# headers.net
KiCad netlist of a schematic drawn in Altium Designer
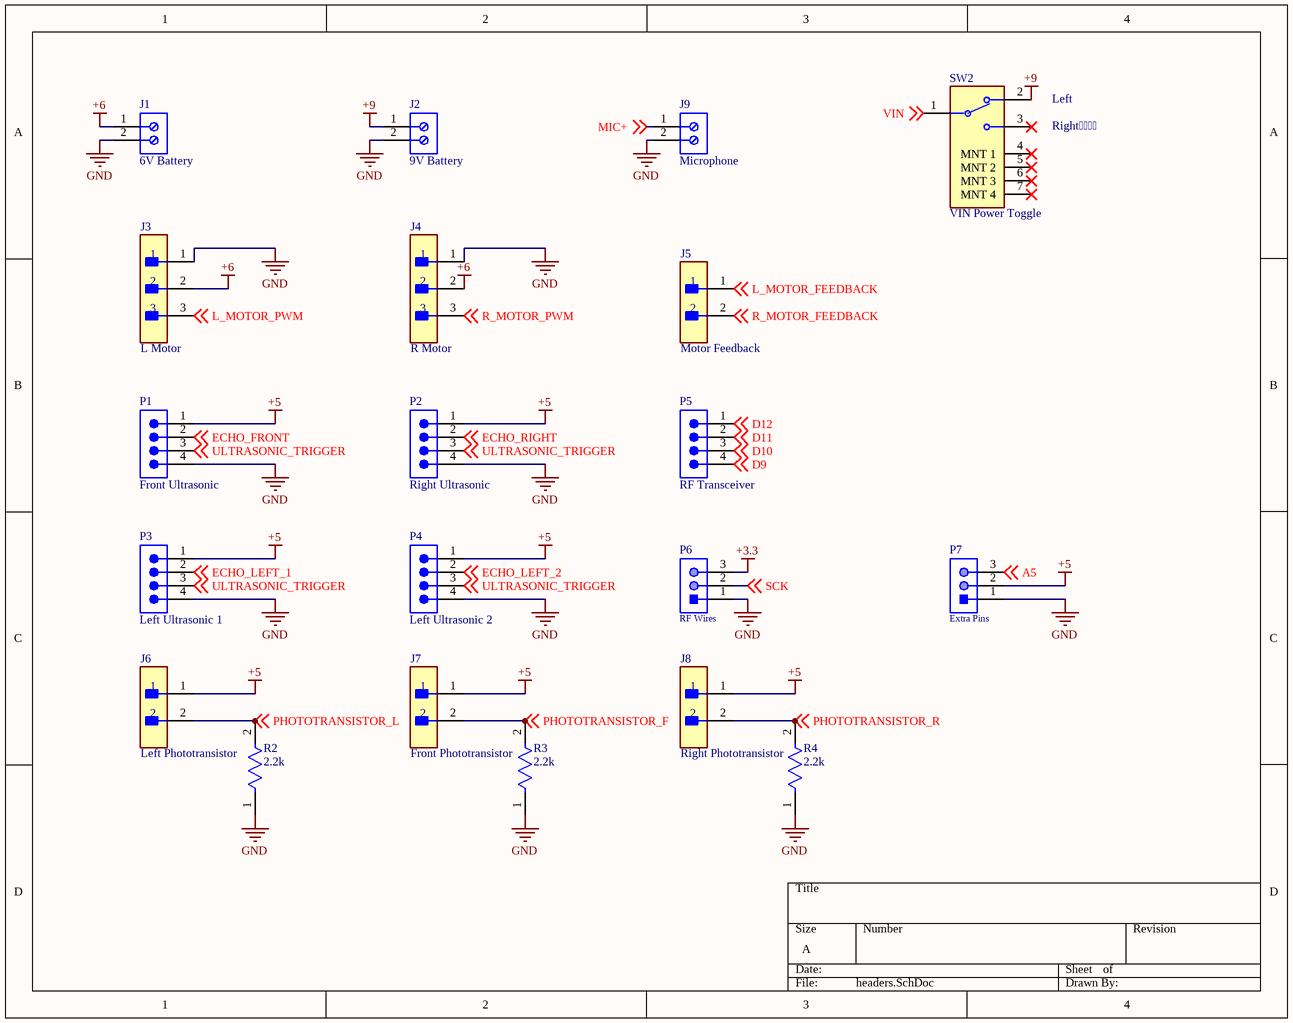
[diagram p0: headers.SchDoc]

(export (version "E")
  (design (tool "Eeschema 10.0.6"))
  (components
    (comp (ref "J1")
      (value "6V Battery")
      (footprint "691103110002")
      (description "Series 1031 - 3.50 mm Horizontal Entry Modular with Pressure Clamp WR-TBL, 2 pin")
      (fields
        (field (name "MANUFACTURER") "Wurth Elektronik")
        (field (name "PART NUMBER") "691103110002")
        (field (name "PUBLISHER") "WurthElektronik")
      )
      (libsource (lib "Altium Content Vault") (part "WE-CN-1P-F-TB2"))
    )
    (comp (ref "J2")
      (value "9V Battery")
      (footprint "691103110002")
      (description "Series 1031 - 3.50 mm Horizontal Entry Modular with Pressure Clamp WR-TBL, 2 pin")
      (fields
        (field (name "MANUFACTURER") "Wurth Elektronik")
        (field (name "PART NUMBER") "691103110002")
        (field (name "PUBLISHER") "WurthElektronik")
      )
      (libsource (lib "Altium Content Vault") (part "WE-CN-1P-F-TB2"))
    )
    (comp (ref "J3")
      (value "L Motor")
      (footprint "FP-5-104935-3-MFG")
      (description "CONN HEADER R/A 3POS 2.54MM")
      (fields (field (name "MPN") "5-104935-3"))
      (libsource (lib "Altium Content Vault") (part "0d3f023dd272f625e17a2be33dea85f"))
    )
    (comp (ref "J4")
      (value "R Motor")
      (footprint "FP-5-104935-3-MFG")
      (description "CONN HEADER R/A 3POS 2.54MM")
      (fields (field (name "MPN") "5-104935-3"))
      (libsource (lib "Altium Content Vault") (part "0d3f023dd272f625e17a2be33dea85f"))
    )
    (comp (ref "J5")
      (value "Motor Feedback")
      (footprint "FP-M20-9990246-MFG")
      (description "CONN HEADER VERT 2POS 2.54MM")
      (fields
        (field (name "OCTOPART") "https://octopart.com/m20-9990246-harwin-2590635")
        (field (name "MANUFACTURER") "Harwin")
      )
      (libsource (lib "Altium Content Vault") (part "3bc925449376181038e59eaffc5286c"))
    )
    (comp (ref "J6")
      (value "Left Phototransistor")
      (footprint "FP-M20-9990246-MFG")
      (description "Connector Header Through Hole 2 position 0.100\" (2.54mm)")
      (fields (field (name "OCTOPART") "https://octopart.com/m20-9990246-harwin-2590635"))
      (libsource (lib "Altium Content Vault") (part "3bc925449376181038e59eaffc5286c"))
    )
    (comp (ref "J7")
      (value "Front Phototransistor")
      (footprint "FP-M20-9990246-MFG")
      (description "Connector Header Through Hole 2 position 0.100\" (2.54mm)")
      (fields (field (name "OCTOPART") "https://octopart.com/m20-9990246-harwin-2590635"))
      (libsource (lib "Altium Content Vault") (part "3bc925449376181038e59eaffc5286c"))
    )
    (comp (ref "J8")
      (value "Right Phototransistor")
      (footprint "FP-M20-9990246-MFG")
      (description "Connector Header Through Hole 2 position 0.100\" (2.54mm)")
      (fields (field (name "OCTOPART") "https://octopart.com/m20-9990246-harwin-2590635"))
      (libsource (lib "Altium Content Vault") (part "3bc925449376181038e59eaffc5286c"))
    )
    (comp (ref "J9")
      (value "Microphone")
      (footprint "691103110002")
      (description "Series 1031 - 3.50 mm Horizontal Entry Modular with Pressure Clamp WR-TBL, 2 pin")
      (fields
        (field (name "MANUFACTURER") "Wurth Elektronik")
        (field (name "PART NUMBER") "691103110002")
        (field (name "PUBLISHER") "WurthElektronik")
      )
      (libsource (lib "Altium Content Vault") (part "WE-CN-1P-F-TB2"))
    )
    (comp (ref "P1")
      (value "Front Ultrasonic")
      (footprint "SMTC-TSW-104-08-X-S")
      (description "0.025\" SQ Post Header, Through-hole, Vertical, -55 to 125 degC, 2.54 mm Pitch, 4-Pin, Male, RoHS")
      (fields (field (name "MANUFACTURER") "Samtec") (field (name "PARTNUMBER") "TSW-104-08-F-S"))
      (libsource (lib "Altium Content Vault") (part "SMTC-TSW-104-08-X-S"))
    )
    (comp (ref "P2")
      (value "Right Ultrasonic")
      (footprint "SMTC-TSW-104-08-X-S")
      (description "0.025\" SQ Post Header, Through-hole, Vertical, -55 to 125 degC, 2.54 mm Pitch, 4-Pin, Male, RoHS")
      (fields (field (name "MANUFACTURER") "Samtec") (field (name "PARTNUMBER") "TSW-104-08-F-S"))
      (libsource (lib "Altium Content Vault") (part "SMTC-TSW-104-08-X-S"))
    )
    (comp (ref "P3")
      (value "Left Ultrasonic 1")
      (footprint "SMTC-TSW-104-08-X-S")
      (description "0.025\" SQ Post Header, Through-hole, Vertical, -55 to 125 degC, 2.54 mm Pitch, 4-Pin, Male, RoHS")
      (fields (field (name "MANUFACTURER") "Samtec") (field (name "PARTNUMBER") "TSW-104-08-F-S"))
      (libsource (lib "Altium Content Vault") (part "SMTC-TSW-104-08-X-S"))
    )
    (comp (ref "P4")
      (value "Left Ultrasonic 2")
      (footprint "SMTC-TSW-104-08-X-S")
      (description "0.025\" SQ Post Header, Through-hole, Vertical, -55 to 125 degC, 2.54 mm Pitch, 4-Pin, Male, RoHS")
      (fields (field (name "MANUFACTURER") "Samtec") (field (name "PARTNUMBER") "TSW-104-08-F-S"))
      (libsource (lib "Altium Content Vault") (part "SMTC-TSW-104-08-X-S"))
    )
    (comp (ref "P5")
      (value "RF Transceiver")
      (footprint "SMTC-TSW-104-08-X-S")
      (description "0.025\" SQ Post Header, Through-hole, Vertical, -55 to 125 degC, 2.54 mm Pitch, 4-Pin, Male, RoHS")
      (fields (field (name "MANUFACTURER") "Samtec") (field (name "PARTNUMBER") "TSW-104-08-F-S"))
      (libsource (lib "Altium Content Vault") (part "SMTC-TSW-104-08-X-S"))
    )
    (comp (ref "P6")
      (value "RF Wires")
      (footprint "61300311121")
      (description "THT Vertical Pin Header WR-PHD, Pitch 2.54 mm, Single Row, 3 pins")
      (fields
        (field (name "PART NUMBER") "61300311121")
        (field (name "MANUFACTURER") "Wurth Elektronik")
        (field (name "PUBLISHER") "WurthElektronik")
      )
      (libsource (lib "Altium Content Vault") (part "WE-CN-1P-M-R3"))
    )
    (comp (ref "P7")
      (value "Extra Pins")
      (footprint "61300311121")
      (description "THT Vertical Pin Header WR-PHD, Pitch 2.54 mm, Single Row, 3 pins")
      (fields
        (field (name "PART NUMBER") "61300311121")
        (field (name "MANUFACTURER") "Wurth Elektronik")
        (field (name "PUBLISHER") "WurthElektronik")
      )
      (libsource (lib "Altium Content Vault") (part "WE-CN-1P-M-R3"))
    )
    (comp (ref "R2")
      (value "2.2k")
      (footprint "FP-CRCW0805-e3-IPC_B")
      (description "RES Thick Film, 2.2kΩ, 1%, 0.125W, 100ppm/°C, 0805")
      (fields (field (name "TOLERANCE") "1%") (field (name "MPN") "CRCW08052K20FKEA"))
      (libsource (lib "Altium Content Vault") (part "1029c3af85768c4190bb7ad29bc67b5"))
    )
    (comp (ref "R3")
      (value "2.2k")
      (footprint "FP-CRCW0805-e3-IPC_B")
      (description "RES Thick Film, 2.2kΩ, 1%, 0.125W, 100ppm/°C, 0805")
      (fields (field (name "TOLERANCE") "1%") (field (name "MPN") "CRCW08052K20FKEA"))
      (libsource (lib "Altium Content Vault") (part "1029c3af85768c4190bb7ad29bc67b5"))
    )
    (comp (ref "R4")
      (value "2.2k")
      (footprint "FP-CRCW0805-e3-IPC_B")
      (description "RES Thick Film, 2.2kΩ, 1%, 0.125W, 100ppm/°C, 0805")
      (fields (field (name "TOLERANCE") "1%") (field (name "MPN") "CRCW08052K20FKEA"))
      (libsource (lib "Altium Content Vault") (part "1029c3af85768c4190bb7ad29bc67b5"))
    )
    (comp (ref "SW2")
      (value "VIN Power Toggle")
      (footprint "FP-PCM12SMTR-MFG")
      (description "SWITCH SLIDE SPDT 300MA 6V")
      (fields (field (name "MPN") "PCM12SMTR"))
      (libsource (lib "Altium Content Vault") (part "1a3f67d7e2b5469b171eeab59ffb4d2"))
    )
  )
  (nets
    (net (code "1") (name "+3.3") (class "Default")
      (node (ref "P6") (pin "3") (pinfunction "3_3") (pintype "passive"))
    )
    (net (code "2") (name "+5") (class "Default")
      (node (ref "J6") (pin "1") (pinfunction "1_1") (pintype "passive"))
      (node (ref "J7") (pin "1") (pinfunction "1_1") (pintype "passive"))
      (node (ref "J8") (pin "1") (pinfunction "1_1") (pintype "passive"))
      (node (ref "P1") (pin "1") (pinfunction "1_1") (pintype "passive"))
      (node (ref "P2") (pin "1") (pinfunction "1_1") (pintype "passive"))
      (node (ref "P3") (pin "1") (pinfunction "1_1") (pintype "passive"))
      (node (ref "P4") (pin "1") (pinfunction "1_1") (pintype "passive"))
      (node (ref "P7") (pin "2") (pinfunction "2_2") (pintype "passive"))
    )
    (net (code "3") (name "+6") (class "Default")
      (node (ref "J1") (pin "1") (pinfunction "1_1") (pintype "passive"))
      (node (ref "J3") (pin "2") (pinfunction "2_2") (pintype "passive"))
      (node (ref "J4") (pin "2") (pinfunction "2_2") (pintype "passive"))
    )
    (net (code "4") (name "+9") (class "Default")
      (node (ref "J2") (pin "1") (pinfunction "1_1") (pintype "passive"))
      (node (ref "SW2") (pin "2") (pinfunction "2_2") (pintype "passive"))
    )
    (net (code "5") (name "A5") (class "Default")
      (node (ref "P7") (pin "3") (pinfunction "3_3") (pintype "passive"))
    )
    (net (code "6") (name "D9") (class "Default")
      (node (ref "P5") (pin "4") (pinfunction "4_4") (pintype "passive"))
    )
    (net (code "7") (name "D10") (class "Default")
      (node (ref "P5") (pin "3") (pinfunction "3_3") (pintype "passive"))
    )
    (net (code "8") (name "D11") (class "Default")
      (node (ref "P5") (pin "2") (pinfunction "2_2") (pintype "passive"))
    )
    (net (code "9") (name "D12") (class "Default")
      (node (ref "P5") (pin "1") (pinfunction "1_1") (pintype "passive"))
    )
    (net (code "10") (name "ECHO_FRONT") (class "Default")
      (node (ref "P1") (pin "2") (pinfunction "2_2") (pintype "passive"))
    )
    (net (code "11") (name "ECHO_LEFT_1") (class "Default")
      (node (ref "P3") (pin "2") (pinfunction "2_2") (pintype "passive"))
    )
    (net (code "12") (name "ECHO_LEFT_2") (class "Default")
      (node (ref "P4") (pin "2") (pinfunction "2_2") (pintype "passive"))
    )
    (net (code "13") (name "ECHO_RIGHT") (class "Default")
      (node (ref "P2") (pin "2") (pinfunction "2_2") (pintype "passive"))
    )
    (net (code "14") (name "GND") (class "Default")
      (node (ref "J1") (pin "2") (pinfunction "2_2") (pintype "passive"))
      (node (ref "J2") (pin "2") (pinfunction "2_2") (pintype "passive"))
      (node (ref "J3") (pin "1") (pinfunction "1_1") (pintype "passive"))
      (node (ref "J4") (pin "1") (pinfunction "1_1") (pintype "passive"))
      (node (ref "J9") (pin "2") (pinfunction "2_2") (pintype "passive"))
      (node (ref "P1") (pin "4") (pinfunction "4_4") (pintype "passive"))
      (node (ref "P2") (pin "4") (pinfunction "4_4") (pintype "passive"))
      (node (ref "P3") (pin "4") (pinfunction "4_4") (pintype "passive"))
      (node (ref "P4") (pin "4") (pinfunction "4_4") (pintype "passive"))
      (node (ref "P6") (pin "1") (pinfunction "1_1") (pintype "passive"))
      (node (ref "P7") (pin "1") (pinfunction "1_1") (pintype "passive"))
      (node (ref "R2") (pin "1") (pinfunction "1_1") (pintype "passive"))
      (node (ref "R3") (pin "1") (pinfunction "1_1") (pintype "passive"))
      (node (ref "R4") (pin "1") (pinfunction "1_1") (pintype "passive"))
    )
    (net (code "15") (name "L_MOTOR_FEEDBACK") (class "Default")
      (node (ref "J5") (pin "1") (pinfunction "1_1") (pintype "passive"))
    )
    (net (code "16") (name "L_MOTOR_PWM") (class "Default")
      (node (ref "J3") (pin "3") (pinfunction "3_3") (pintype "passive"))
    )
    (net (code "17") (name "MIC+") (class "Default")
      (node (ref "J9") (pin "1") (pinfunction "1_1") (pintype "passive"))
    )
    (net (code "18") (name "PHOTOTRANSISTOR_F") (class "Default")
      (node (ref "J7") (pin "2") (pinfunction "2_2") (pintype "passive"))
      (node (ref "R3") (pin "2") (pinfunction "2_2") (pintype "passive"))
    )
    (net (code "19") (name "PHOTOTRANSISTOR_L") (class "Default")
      (node (ref "J6") (pin "2") (pinfunction "2_2") (pintype "passive"))
      (node (ref "R2") (pin "2") (pinfunction "2_2") (pintype "passive"))
    )
    (net (code "20") (name "PHOTOTRANSISTOR_R") (class "Default")
      (node (ref "J8") (pin "2") (pinfunction "2_2") (pintype "passive"))
      (node (ref "R4") (pin "2") (pinfunction "2_2") (pintype "passive"))
    )
    (net (code "21") (name "R_MOTOR_FEEDBACK") (class "Default")
      (node (ref "J5") (pin "2") (pinfunction "2_2") (pintype "passive"))
    )
    (net (code "22") (name "R_MOTOR_PWM") (class "Default")
      (node (ref "J4") (pin "3") (pinfunction "3_3") (pintype "passive"))
    )
    (net (code "23") (name "SCK") (class "Default")
      (node (ref "P6") (pin "2") (pinfunction "2_2") (pintype "passive"))
    )
    (net (code "24") (name "ULTRASONIC_TRIGGER") (class "Default")
      (node (ref "P1") (pin "3") (pinfunction "3_3") (pintype "passive"))
      (node (ref "P2") (pin "3") (pinfunction "3_3") (pintype "passive"))
      (node (ref "P3") (pin "3") (pinfunction "3_3") (pintype "passive"))
      (node (ref "P4") (pin "3") (pinfunction "3_3") (pintype "passive"))
    )
    (net (code "25") (name "VIN") (class "Default")
      (node (ref "SW2") (pin "1") (pinfunction "1_1") (pintype "passive"))
    )
    (net (code "26") (name "unconnected-(SW2-MNT_1-Pad4)") (class "Default")
      (node (ref "SW2") (pin "4") (pinfunction "MNT_1_4") (pintype "passive+no_connect"))
    )
    (net (code "27") (name "unconnected-(SW2-MNT_2-Pad5)") (class "Default")
      (node (ref "SW2") (pin "5") (pinfunction "MNT_2_5") (pintype "passive+no_connect"))
    )
    (net (code "28") (name "unconnected-(SW2-MNT_3-Pad6)") (class "Default")
      (node (ref "SW2") (pin "6") (pinfunction "MNT_3_6") (pintype "passive+no_connect"))
    )
    (net (code "29") (name "unconnected-(SW2-MNT_4-Pad7)") (class "Default")
      (node (ref "SW2") (pin "7") (pinfunction "MNT_4_7") (pintype "passive+no_connect"))
    )
    (net (code "30") (name "unconnected-(SW2-Pad3)") (class "Default")
      (node (ref "SW2") (pin "3") (pinfunction "3_3") (pintype "passive+no_connect"))
    )
  )
)
